# USB.net
KiCad netlist of a schematic drawn in Altium Designer
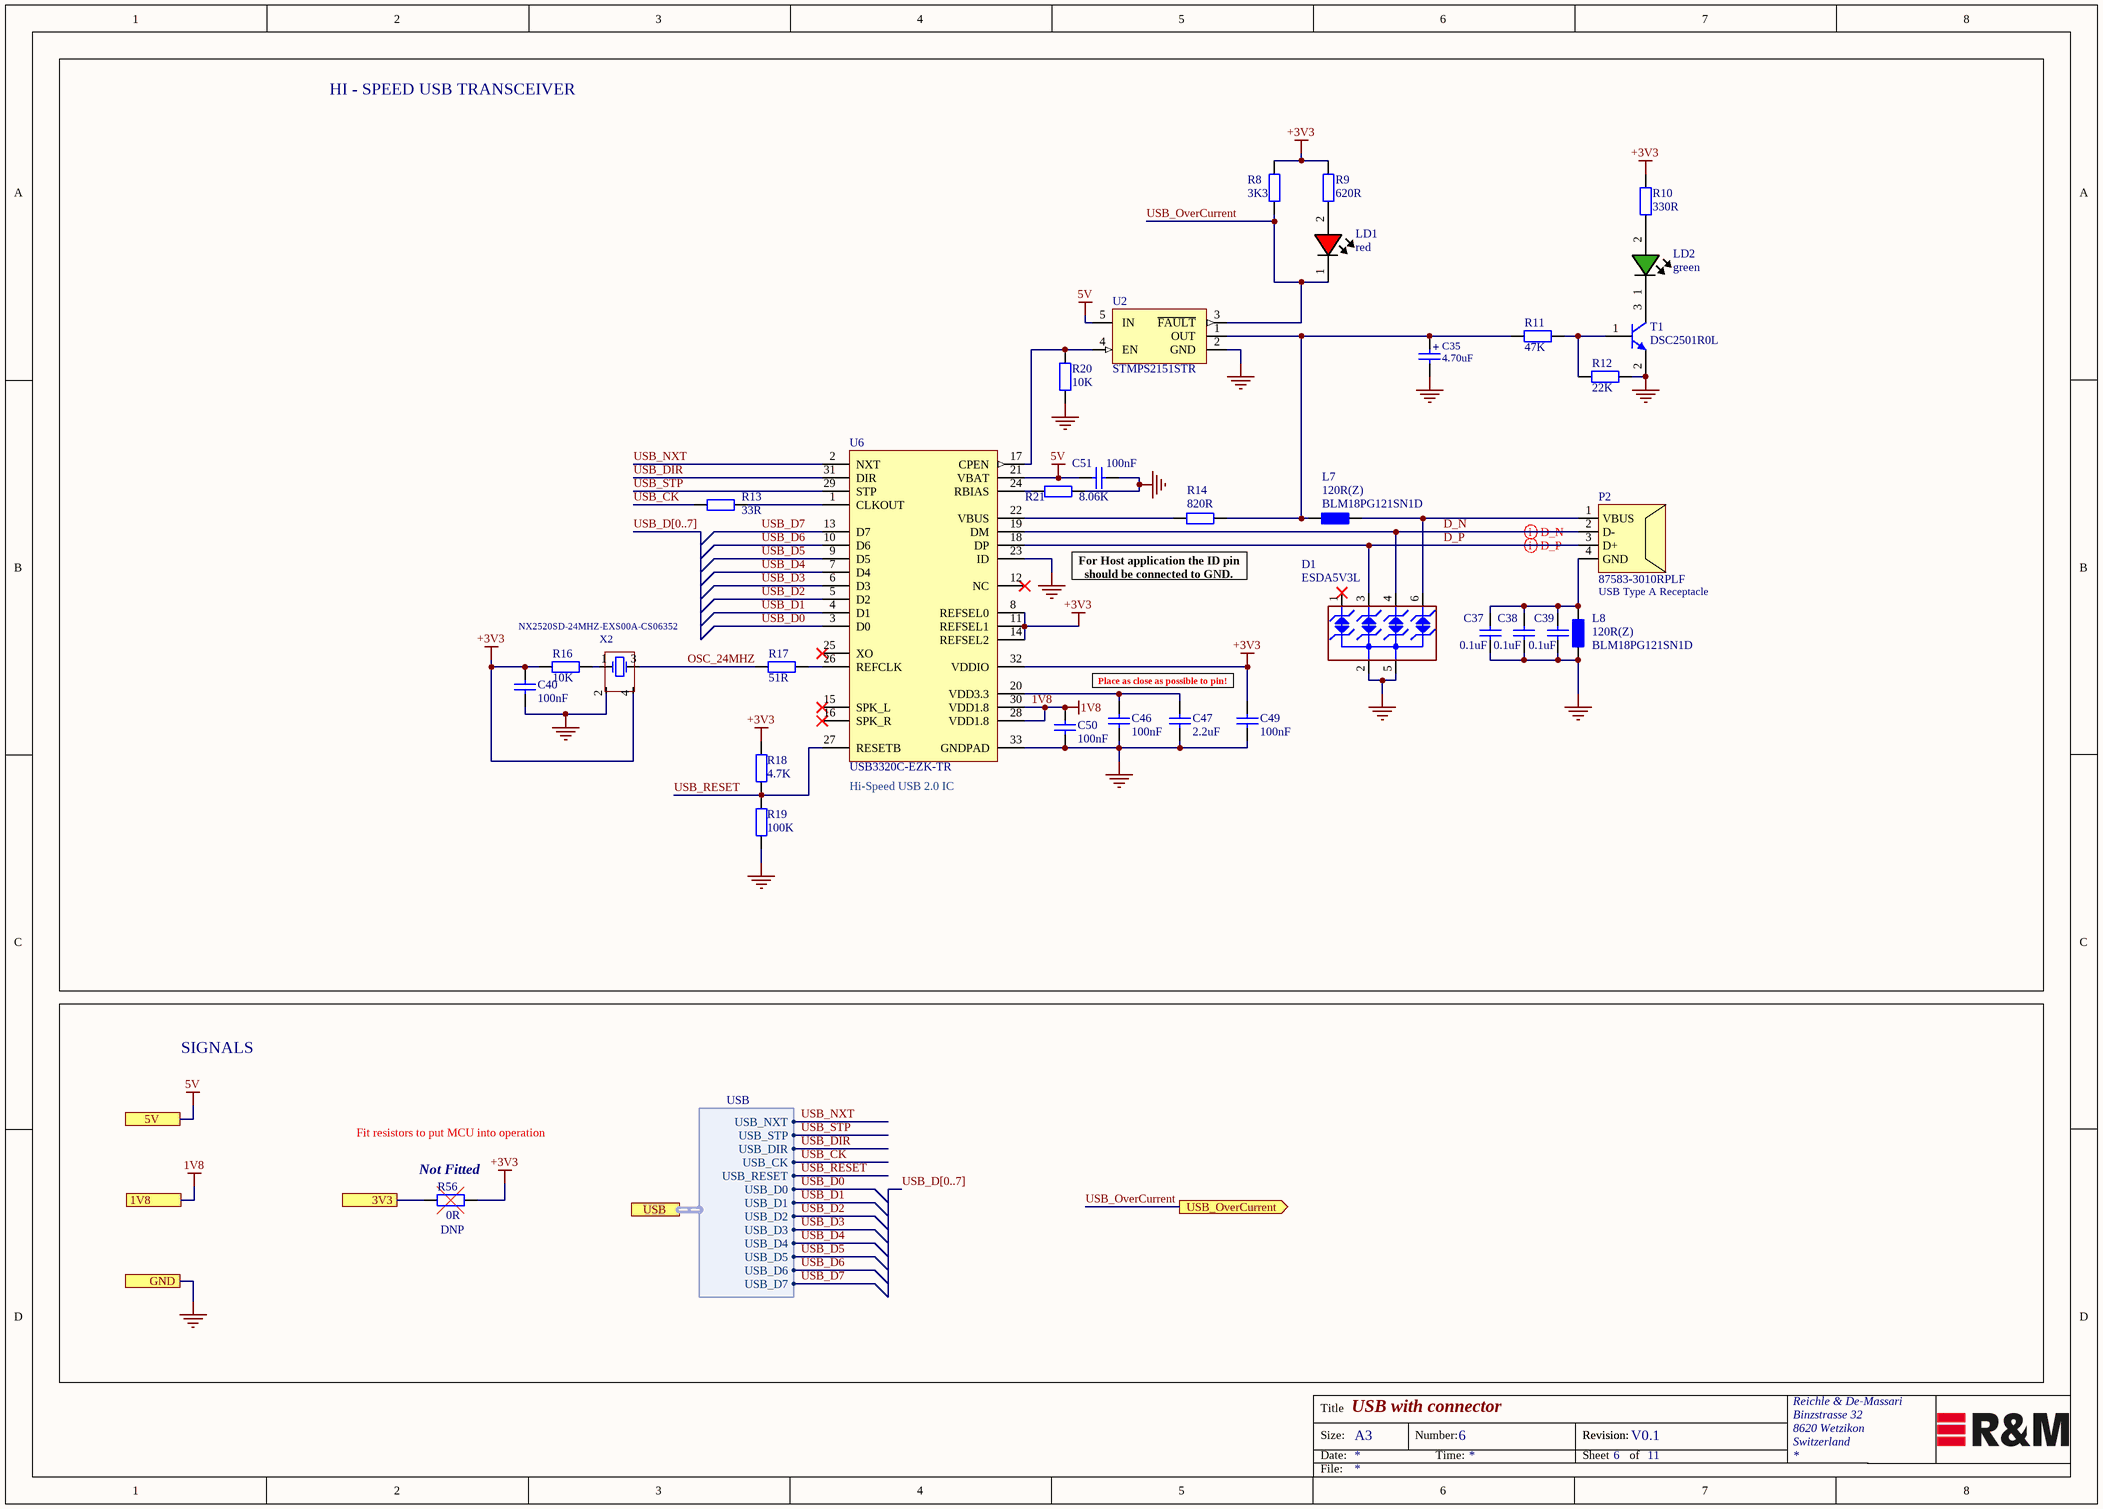
[diagram p0: USB.SchDoc]

(export (version "E")
  (design (tool "Eeschema 10.0.6"))
  (components
    (comp (ref "C35")
      (value "4.70uF")
      (footprint "CAPC1608X90")
      (description "4.7µF Molded Tantalum Capacitors 6.3V 0603 (1608 Metric) 7.5Ohm")
      (fields (field (name "MANUFACTURER") "AVX Corporation") (field (name "VOLTAGE") "6.3V"))
      (libsource (lib "RDM_ALT_SCH") (part "Cap_4.7uF_0603_6V3_Tantal"))
    )
    (comp (ref "C37")
      (value "0.1uF")
      (footprint "Ceramic Capacitor 0402 EIA")
      (description "0.1µF ±20% 16V Ceramic Capacitor X7R 0402 (1005 Metric)")
      (fields (field (name "TOLERANCE") "20%") (field (name "VOLTAGE") "16VDC"))
      (libsource (lib "RDM_ALT_SCH") (part "Cap_0.1uF_0402_16V"))
    )
    (comp (ref "C38")
      (value "0.1uF")
      (footprint "Ceramic Capacitor 0402 EIA")
      (description "0.1µF ±20% 16V Ceramic Capacitor X7R 0402 (1005 Metric)")
      (fields (field (name "TOLERANCE") "20%") (field (name "VOLTAGE") "16VDC"))
      (libsource (lib "RDM_ALT_SCH") (part "Cap_0.1uF_0402_16V"))
    )
    (comp (ref "C39")
      (value "0.1uF")
      (footprint "Ceramic Capacitor 0402 EIA")
      (description "0.1µF ±20% 16V Ceramic Capacitor X7R 0402 (1005 Metric)")
      (fields (field (name "TOLERANCE") "20%") (field (name "VOLTAGE") "16VDC"))
      (libsource (lib "RDM_ALT_SCH") (part "Cap_0.1uF_0402_16V"))
    )
    (comp (ref "C40")
      (value "100nF")
      (footprint "Ceramic Capacitor 0402 EIA")
      (description "0,1µF ±10% 10V Keramikkondensatoren X7R 0402 (1005 metrisch)")
      (fields (field (name "MANUFACTURER") "Samsung"))
      (libsource (lib "RDM_ALT_SCH") (part "Cap_100nF_0402_10V"))
    )
    (comp (ref "C46")
      (value "100nF")
      (footprint "Ceramic Capacitor 0402 EIA")
      (description "0,1µF ±10% 10V Keramikkondensatoren X7R 0402 (1005 metrisch)")
      (fields (field (name "MANUFACTURER") "Samsung"))
      (libsource (lib "RDM_ALT_SCH") (part "Cap_100nF_0402_10V"))
    )
    (comp (ref "C47")
      (value "2.2uF")
      (footprint "Ceramic Capacitor 0402 EIA")
      (description "Multilayer Ceramic Capacitors MLCC - SMD/SMT 0402 2.2uF 6.3volts *Derate Voltage/Temp")
      (fields (field (name "TOLERANCE") "±20%") (field (name "VOLTAGE") "6.3VDC"))
      (libsource (lib "RDM_ALT_SCH") (part "Cap_2.2uF_0402_6.3V"))
    )
    (comp (ref "C49")
      (value "100nF")
      (footprint "Ceramic Capacitor 0402 EIA")
      (description "0,1µF ±10% 10V Keramikkondensatoren X7R 0402 (1005 metrisch)")
      (fields (field (name "MANUFACTURER") "Samsung"))
      (libsource (lib "RDM_ALT_SCH") (part "Cap_100nF_0402_10V"))
    )
    (comp (ref "C50")
      (value "100nF")
      (footprint "Ceramic Capacitor 0402 EIA")
      (description "0,1µF ±10% 10V Keramikkondensatoren X7R 0402 (1005 metrisch)")
      (fields (field (name "MANUFACTURER") "Samsung"))
      (libsource (lib "RDM_ALT_SCH") (part "Cap_100nF_0402_10V"))
    )
    (comp (ref "C51")
      (value "100nF")
      (footprint "Ceramic Capacitor 0402 EIA")
      (description "0,1µF ±10% 10V Keramikkondensatoren X7R 0402 (1005 metrisch)")
      (fields (field (name "MANUFACTURER") "Samsung"))
      (libsource (lib "RDM_ALT_SCH") (part "Cap_100nF_0402_10V"))
    )
    (comp (ref "D1")
      (value "ESDA5V3L")
      (footprint "SOT23-6L")
      (description "Clamp Ipp Tvs Diode Surface Mount SOT-23-6 SMD, used e.g in ESD protection for USB")
      (fields (field (name "MANUFACTURER") "STMicroelectronics") (field (name "VOLTAGE") "6.1V"))
      (libsource (lib "RDM_ALT_SCH") (part "ESDA6V1BC6"))
    )
    (comp (ref "L7")
      (value "120R(Z)")
      (footprint "Inductor 0603 EIA")
      (description "120 Ohms @ 100MHz 1 Power Line Ferrite Bead 0603 (1608 Metric) 2A 50mOhm")
      (fields
        (field (name "MANUFACTURER") "Murata Electronics")
        (field (name "MANUFACTURER PARTNR") "BLM18PG121SN1D")
      )
      (libsource (lib "RDM_ALT_SCH") (part "Ferrit_Bead_0603_BLM18PG121SN1D"))
    )
    (comp (ref "L8")
      (value "120R(Z)")
      (footprint "Inductor 0603 EIA")
      (description "120 Ohms @ 100MHz 1 Power Line Ferrite Bead 0603 (1608 Metric) 2A 50mOhm")
      (fields
        (field (name "MANUFACTURER") "Murata Electronics")
        (field (name "MANUFACTURER PARTNR") "BLM18PG121SN1D")
      )
      (libsource (lib "") (part "Ferrit_Bead_0603_BLM18PG121SN1D_1"))
    )
    (comp (ref "LD1")
      (value "red")
      (footprint "LED_APHHS1005CGCK")
      (description "Red 630nm LED Indication - Discrete 1.95V 0402 (1005 Metric)")
      (fields (field (name "MANUFACTURER") "Kingbright") (field (name "VOLTAGE") "1.95V (forward)"))
      (libsource (lib "RDM_ALT_SCH") (part "LED_RED_0402"))
    )
    (comp (ref "LD2")
      (value "green")
      (footprint "LED_APHHS1005CGCK")
      (description "Green 570nm LED Indication - Discrete 2.1V 0402 (1005 Metric)")
      (fields (field (name "MANUFACTURER") "Kingbright") (field (name "VOLTAGE") "2.1V (forward)"))
      (libsource (lib "RDM_ALT_SCH") (part "LED_GREEN_0402"))
    )
    (comp (ref "P2")
      (value "87583-3010RPLF")
      (footprint "CONN_RCPT_USB_TYPE_A")
      (description "USB - A USB 2.0 Receptacle Connector 4 Position Surface Mount, Right Angle")
      (fields (field (name "MANUFACTURER") "Amphenol ICC"))
      (libsource (lib "RDM_ALT_SCH") (part "CONN_USB_TYPE_A_1"))
    )
    (comp (ref "R8")
      (value "3K3")
      (footprint "Resistor 0402 EIA")
      (description "3.3 kOhms ±0.1% 0.063W, 1/16W Chip Resistor 0402 (1005 Metric) Automotive AEC-Q200 Thin Film")
      (fields
        (field (name "MANUFACTURER") "Panasonic Electronic Components")
        (field (name "POWER") "0.063W, 1/16W")
      )
      (libsource (lib "RDM_ALT_SCH") (part "Res_3K3_0402"))
    )
    (comp (ref "R9")
      (value "620R")
      (footprint "Resistor 0402 EIA")
      (description "620Ohm, SMD 0402,  1/16W  0.5%")
      (fields (field (name "MANUFACTURER") "Susumu") (field (name "POWER") "62.5mW"))
      (libsource (lib "RDM_ALT_SCH") (part "Res_620R_0402"))
    )
    (comp (ref "R10")
      (value "330R")
      (footprint "Resistor 0402 EIA")
      (description "330 Ohms ±0.1% 0.063W, 1/16W Chip Resistor 0402 (1005 Metric) Automotive AEC-Q200 Thin Film")
      (fields
        (field (name "MANUFACTURER") "Panasonic Electronic Components")
        (field (name "POWER") "0.063W, 1/16W")
      )
      (libsource (lib "RDM_ALT_SCH") (part "Res_330R_0402"))
    )
    (comp (ref "R11")
      (value "47K")
      (footprint "Resistor 0402 EIA")
      (fields
        (field (name "TOLERANCE") "5%")
        (field (name "POWER") "62.5mW")
        (field (name "MANUFACTURER") "TE Connectivity")
      )
      (libsource (lib "RDM_ALT_SCH") (part "Res_47K_0402"))
    )
    (comp (ref "R12")
      (value "22K")
      (footprint "Resistor 0402 EIA")
      (description "22 kOhms ±5%  0402 (1005 metrisch) Thick Film")
      (fields (field (name "TOLERANCE") "5%") (field (name "POWER") "0.063W, 1/16W"))
      (libsource (lib "RDM_ALT_SCH") (part "Res_22K_0402"))
    )
    (comp (ref "R13")
      (value "33R")
      (footprint "Resistor 0402 EIA")
      (description "33 Ohms ±0.1% 0.063W, 1/16W Chip Resistor 0402 (1005 Metric) Thin Film")
      (fields (field (name "MANUFACTURER") "TE Connectivity") (field (name "POWER") "0.063W, 1/16W"))
      (libsource (lib "RDM_ALT_SCH") (part "Res_33R_0402"))
    )
    (comp (ref "R14")
      (value "820R")
      (footprint "Resistor 0402 EIA")
      (description "820 Ohms ±1% 0.1W, 1/10W 0402 Thick Film")
      (fields (field (name "TOLERANCE") "1%") (field (name "POWER") "0.1W, 1/10W"))
      (libsource (lib "RDM_ALT_SCH") (part "Res_820R_0402"))
    )
    (comp (ref "R16")
      (value "10K")
      (footprint "Resistor 0402 EIA")
      (description "SMD 10K ohm 1% 50V General Purpose")
      (fields (field (name "TOLERANCE") "1%") (field (name "POWER") "63mW"))
      (libsource (lib "") (part "Res_10K_0402_1"))
    )
    (comp (ref "R17")
      (value "51R")
      (footprint "Resistor 0402 EIA")
      (description "51 Ohms ±5% 0.063W, 1/16W Chip Resistor 0402 (1005 Metric) , Thick Film")
      (fields (field (name "TOLERANCE") "5%") (field (name "POWER") "62.5mW"))
      (libsource (lib "RDM_ALT_SCH") (part "Res_51R_0402"))
    )
    (comp (ref "R18")
      (value "4.7K")
      (footprint "Resistor 0402 EIA")
      (description "4.7 kOhms ±5% 0.063W, 1/16W Chip Resistor 0402 (1005 Metric) Moisture Resistant Thick Film")
      (fields (field (name "TOLERANCE") "±5%") (field (name "POWER") "0.063W, 1/16W"))
      (libsource (lib "RDM_ALT_SCH") (part "Res_4K7_0402"))
    )
    (comp (ref "R19")
      (value "100K")
      (footprint "Resistor 0402 EIA")
      (description "100 kOhms ±0,1% 0,063W, 1/16W Chip-Widerstand 0402 (1005 metrisch) Dünnschicht")
      (fields (field (name "TOLERANCE") "±0.1%") (field (name "POWER") "0,063W, 1/16W"))
      (libsource (lib "RDM_ALT_SCH") (part "Res_100K_0402"))
    )
    (comp (ref "R20")
      (value "10K")
      (footprint "Resistor 0402 EIA")
      (description "SMD 10K ohm 1% 50V General Purpose")
      (fields (field (name "TOLERANCE") "1%") (field (name "POWER") "63mW"))
      (libsource (lib "RDM_ALT_SCH") (part "Res_10K_0402"))
    )
    (comp (ref "R21")
      (value "8.06K")
      (footprint "Resistor 0402 EIA")
      (description "8.06 kOhms ±1% 0.063W, 1/16W Chip Resistor 0402 (1005 Metric) Moisture Resistant Thick Film")
      (fields (field (name "TOLERANCE") "±1%") (field (name "POWER") "0.063W, 1/16W"))
      (libsource (lib "RDM_ALT_SCH") (part "Res_8K06_0402"))
    )
    (comp (ref "R56")
      (value "DNP")
      (footprint "Resistor 0805 EIA")
      (description "Resistor: do not populate")
      (fields (field (name "MANUFACTURER") "do not populate"))
      (libsource (lib "RDM_ALT_SCH") (part "Res_DNP_0805"))
    )
    (comp (ref "T1")
      (value "DSC2501R0L")
      (footprint "SOT-23/TO-236AA")
      (description "Bipolar (BJT) Transistor NPN 20V 500mA 150MHz 200mW Surface Mount Mini3-G3-B-B")
      (fields (field (name "MANUFACTURER") "Panasonic Electronic Components") (field (name "VOLTAGE") "20V"))
      (libsource (lib "RDM_ALT_SCH") (part "BJT_NPN_20V"))
    )
    (comp (ref "U2")
      (value "STMPS2151STR")
      (footprint "SOT23-5L")
      (description "Power Switch/Driver 1:1 N-Kanal 500mA SOT-23-5,  STMicroelectronics")
      (fields (field (name "MANUFACTURER") "STMicroelectronics") (field (name "VOLTAGE") "2,7V ~ 5,5V"))
      (libsource (lib "RDM_ALT_SCH") (part "STMPS2151STR"))
    )
    (comp (ref "U6")
      (value "USB3320C-EZK-TR")
      (footprint "QFN32_0R5_5X5")
      (description "USB3320C,  Hi-Speed USB Host, Device or OTG PHY with ULPI Low Pin Interface,  32-QFN (5x5)")
      (fields (field (name "MANUFACTURER") "Microchip") (field (name "VOLTAGE") "1.8V ~ 3.3V"))
      (libsource (lib "RDM_ALT_SCH") (part "USB3320C-EZK"))
    )
    (comp (ref "X2")
      (value "NX2520SD-24MHZ-EXS00A-CS06352")
      (footprint "NX2520SD-24MHZ-EX")
      (description "24MHz ±15ppm Crystal 12pF 50 Ohms 4-SMD, No Lead")
      (fields (field (name "MANUFACTURER") "NDK America, Inc."))
      (libsource (lib "RDM_ALT_SCH") (part "CRYSTAL_4Pad_NX2520SD-24MHZ"))
    )
  )
  (nets
    (net (code "2") (name "+3V3") (class "Default")
      (node (ref "C40") (pin "2") (pinfunction "2_2") (pintype "passive"))
      (node (ref "C49") (pin "2") (pinfunction "2_2") (pintype "passive"))
      (node (ref "R10") (pin "1") (pinfunction "1_1") (pintype "passive"))
      (node (ref "R16") (pin "1") (pinfunction "1_1") (pintype "passive"))
      (node (ref "R18") (pin "1") (pinfunction "1_1") (pintype "passive"))
      (node (ref "R56") (pin "2") (pinfunction "2_2") (pintype "passive"))
      (node (ref "R8") (pin "2") (pinfunction "2_2") (pintype "passive"))
      (node (ref "R9") (pin "1") (pinfunction "1_1") (pintype "passive"))
      (node (ref "U6") (pin "11") (pinfunction "REFSEL1_11") (pintype "passive"))
      (node (ref "U6") (pin "14") (pinfunction "REFSEL2_14") (pintype "passive"))
      (node (ref "U6") (pin "32") (pinfunction "VDDIO_32") (pintype "passive"))
      (node (ref "U6") (pin "8") (pinfunction "REFSEL0_8") (pintype "passive"))
      (node (ref "X2") (pin "4") (pinfunction "OSC3_4") (pintype "passive"))
    )
    (net (code "3") (name "/3V3") (class "Default")
      (node (ref "R56") (pin "1") (pinfunction "1_1") (pintype "passive"))
    )
    (net (code "4") (name "/D_N") (class "Default")
      (node (ref "D1") (pin "4") (pinfunction "IO3_4") (pintype "passive"))
      (node (ref "P2") (pin "2") (pinfunction "D-_2") (pintype "passive"))
      (node (ref "U6") (pin "19") (pinfunction "DM_19") (pintype "passive"))
    )
    (net (code "5") (name "/D_P") (class "Default")
      (node (ref "D1") (pin "3") (pinfunction "GND_3") (pintype "passive"))
      (node (ref "P2") (pin "3") (pinfunction "D+_3") (pintype "passive"))
      (node (ref "U6") (pin "18") (pinfunction "DP_18") (pintype "passive"))
    )
    (net (code "6") (name "/OSC_24MHZ") (class "Default")
      (node (ref "R17") (pin "1") (pinfunction "1_1") (pintype "passive"))
      (node (ref "X2") (pin "3") (pinfunction "OSC2_3") (pintype "passive"))
    )
    (net (code "7") (name "/USB_CK") (class "Default")
      (node (ref "R13") (pin "1") (pinfunction "1_1") (pintype "passive"))
    )
    (net (code "8") (name "/USB_D0") (class "Default")
      (node (ref "U6") (pin "3") (pinfunction "D0_3") (pintype "passive"))
    )
    (net (code "9") (name "/USB_D1") (class "Default")
      (node (ref "U6") (pin "4") (pinfunction "D1_4") (pintype "passive"))
    )
    (net (code "10") (name "/USB_D2") (class "Default")
      (node (ref "U6") (pin "5") (pinfunction "D2_5") (pintype "passive"))
    )
    (net (code "11") (name "/USB_D3") (class "Default")
      (node (ref "U6") (pin "6") (pinfunction "D3_6") (pintype "passive"))
    )
    (net (code "12") (name "/USB_D4") (class "Default")
      (node (ref "U6") (pin "7") (pinfunction "D4_7") (pintype "passive"))
    )
    (net (code "13") (name "/USB_D5") (class "Default")
      (node (ref "U6") (pin "9") (pinfunction "D5_9") (pintype "passive"))
    )
    (net (code "14") (name "/USB_D6") (class "Default")
      (node (ref "U6") (pin "10") (pinfunction "D6_10") (pintype "passive"))
    )
    (net (code "15") (name "/USB_D7") (class "Default")
      (node (ref "U6") (pin "13") (pinfunction "D7_13") (pintype "passive"))
    )
    (net (code "16") (name "/USB_DIR") (class "Default")
      (node (ref "U6") (pin "31") (pinfunction "DIR_31") (pintype "passive"))
    )
    (net (code "18") (name "/USB_NXT") (class "Default")
      (node (ref "U6") (pin "2") (pinfunction "NXT_2") (pintype "passive"))
    )
    (net (code "19") (name "/USB_OverCurrent") (class "Default")
      (node (ref "LD1") (pin "1") (pinfunction "1_1") (pintype "passive"))
      (node (ref "R8") (pin "1") (pinfunction "1_1") (pintype "passive"))
      (node (ref "U2") (pin "3") (pinfunction "~{FAULT}_3") (pintype "output"))
    )
    (net (code "20") (name "/USB_RESET") (class "Default")
      (node (ref "R18") (pin "2") (pinfunction "2_2") (pintype "passive"))
      (node (ref "R19") (pin "1") (pinfunction "1_1") (pintype "passive"))
      (node (ref "U6") (pin "27") (pinfunction "RESETB_27") (pintype "passive"))
    )
    (net (code "21") (name "/USB_STP") (class "Default")
      (node (ref "U6") (pin "29") (pinfunction "STP_29") (pintype "passive"))
    )
    (net (code "23") (name "1V8") (class "Default")
      (node (ref "C50") (pin "2") (pinfunction "2_2") (pintype "passive"))
      (node (ref "U6") (pin "28") (pinfunction "VDD1.8_28") (pintype "passive"))
      (node (ref "U6") (pin "30") (pinfunction "VDD1.8_30") (pintype "passive"))
    )
    (net (code "24") (name "5V") (class "Default")
      (node (ref "C51") (pin "2") (pinfunction "2_2") (pintype "passive"))
      (node (ref "U2") (pin "5") (pinfunction "IN_5") (pintype "passive"))
      (node (ref "U6") (pin "21") (pinfunction "VBAT_21") (pintype "passive"))
    )
    (net (code "25") (name "GND") (class "Default")
      (node (ref "C35") (pin "2") (pinfunction "Neg_2") (pintype "passive"))
      (node (ref "C37") (pin "1") (pinfunction "1_1") (pintype "passive"))
      (node (ref "C38") (pin "1") (pinfunction "1_1") (pintype "passive"))
      (node (ref "C39") (pin "1") (pinfunction "1_1") (pintype "passive"))
      (node (ref "C40") (pin "1") (pinfunction "1_1") (pintype "passive"))
      (node (ref "C46") (pin "1") (pinfunction "1_1") (pintype "passive"))
      (node (ref "C47") (pin "1") (pinfunction "1_1") (pintype "passive"))
      (node (ref "C49") (pin "1") (pinfunction "1_1") (pintype "passive"))
      (node (ref "C50") (pin "1") (pinfunction "1_1") (pintype "passive"))
      (node (ref "C51") (pin "1") (pinfunction "1_1") (pintype "passive"))
      (node (ref "D1") (pin "2") (pinfunction "IO2_2") (pintype "passive"))
      (node (ref "D1") (pin "5") (pinfunction "IO4_5") (pintype "passive"))
      (node (ref "L8") (pin "1") (pinfunction "1_1") (pintype "passive"))
      (node (ref "R12") (pin "2") (pinfunction "2_2") (pintype "passive"))
      (node (ref "R19") (pin "2") (pinfunction "2_2") (pintype "passive"))
      (node (ref "R20") (pin "2") (pinfunction "2_2") (pintype "passive"))
      (node (ref "R21") (pin "2") (pinfunction "2_2") (pintype "passive"))
      (node (ref "T1") (pin "2") (pinfunction "E_2") (pintype "passive"))
      (node (ref "U2") (pin "2") (pinfunction "GND_2") (pintype "passive"))
      (node (ref "U6") (pin "23") (pinfunction "ID_23") (pintype "passive"))
      (node (ref "U6") (pin "33") (pinfunction "GNDPAD_33") (pintype "passive"))
      (node (ref "X2") (pin "2") (pinfunction "OSC2_2") (pintype "passive"))
    )
    (net (code "26") (name "Net-(C35-Pos)") (class "Default")
      (node (ref "C35") (pin "1") (pinfunction "Pos_1") (pintype "passive"))
      (node (ref "L7") (pin "1") (pinfunction "1_1") (pintype "passive"))
      (node (ref "R11") (pin "1") (pinfunction "1_1") (pintype "passive"))
      (node (ref "R14") (pin "2") (pinfunction "2_2") (pintype "passive"))
      (node (ref "U2") (pin "1") (pinfunction "OUT_1") (pintype "passive"))
    )
    (net (code "27") (name "Net-(D1-NC)") (class "Default")
      (node (ref "D1") (pin "6") (pinfunction "NC_6") (pintype "passive"))
      (node (ref "L7") (pin "2") (pinfunction "2_2") (pintype "passive"))
      (node (ref "P2") (pin "1") (pinfunction "VBUS_1") (pintype "passive"))
    )
    (net (code "28") (name "Net-(LD2-Pad2)") (class "Default")
      (node (ref "LD2") (pin "2") (pinfunction "2_2") (pintype "passive"))
      (node (ref "R10") (pin "2") (pinfunction "2_2") (pintype "passive"))
    )
    (net (code "29") (name "Net-(P2-GND)") (class "Default")
      (node (ref "C37") (pin "2") (pinfunction "2_2") (pintype "passive"))
      (node (ref "C38") (pin "2") (pinfunction "2_2") (pintype "passive"))
      (node (ref "C39") (pin "2") (pinfunction "2_2") (pintype "passive"))
      (node (ref "L8") (pin "2") (pinfunction "2_2") (pintype "passive"))
      (node (ref "P2") (pin "4") (pinfunction "GND_4") (pintype "passive"))
    )
    (net (code "30") (name "Net-(T1-B)") (class "Default")
      (node (ref "R11") (pin "2") (pinfunction "2_2") (pintype "passive"))
      (node (ref "R12") (pin "1") (pinfunction "1_1") (pintype "passive"))
      (node (ref "T1") (pin "1") (pinfunction "B_1") (pintype "passive"))
    )
    (net (code "31") (name "Net-(U2-EN)") (class "Default")
      (node (ref "R20") (pin "1") (pinfunction "1_1") (pintype "passive"))
      (node (ref "U2") (pin "4") (pinfunction "EN_4") (pintype "input"))
      (node (ref "U6") (pin "17") (pinfunction "CPEN_17") (pintype "output"))
    )
    (net (code "32") (name "Net-(U6-CLKOUT)") (class "Default")
      (node (ref "R13") (pin "2") (pinfunction "2_2") (pintype "passive"))
      (node (ref "U6") (pin "1") (pinfunction "CLKOUT_1") (pintype "passive"))
    )
    (net (code "33") (name "Net-(U6-RBIAS)") (class "Default")
      (node (ref "R21") (pin "1") (pinfunction "1_1") (pintype "passive"))
      (node (ref "U6") (pin "24") (pinfunction "RBIAS_24") (pintype "passive"))
    )
    (net (code "34") (name "Net-(U6-REFCLK)") (class "Default")
      (node (ref "R17") (pin "2") (pinfunction "2_2") (pintype "passive"))
      (node (ref "U6") (pin "26") (pinfunction "REFCLK_26") (pintype "passive"))
    )
    (net (code "35") (name "Net-(U6-VBUS)") (class "Default")
      (node (ref "R14") (pin "1") (pinfunction "1_1") (pintype "passive"))
      (node (ref "U6") (pin "22") (pinfunction "VBUS_22") (pintype "passive"))
    )
    (net (code "36") (name "Net-(U6-VDD3.3)") (class "Default")
      (node (ref "C46") (pin "2") (pinfunction "2_2") (pintype "passive"))
      (node (ref "C47") (pin "2") (pinfunction "2_2") (pintype "passive"))
      (node (ref "U6") (pin "20") (pinfunction "VDD3.3_20") (pintype "passive"))
    )
    (net (code "37") (name "Net-(X2-OSC1)") (class "Default")
      (node (ref "R16") (pin "2") (pinfunction "2_2") (pintype "passive"))
      (node (ref "X2") (pin "1") (pinfunction "OSC1_1") (pintype "passive"))
    )
    (net (code "38") (name "unconnected-(D1-IO1-Pad1)") (class "Default")
      (node (ref "D1") (pin "1") (pinfunction "IO1_1") (pintype "passive+no_connect"))
    )
    (net (code "39") (name "unconnected-(LD1-Pad2)") (class "Default")
      (node (ref "LD1") (pin "2") (pinfunction "2_2") (pintype "passive"))
    )
    (net (code "40") (name "unconnected-(LD2-Pad1)") (class "Default")
      (node (ref "LD2") (pin "1") (pinfunction "1_1") (pintype "passive"))
    )
    (net (code "41") (name "unconnected-(R9-Pad2)") (class "Default")
      (node (ref "R9") (pin "2") (pinfunction "2_2") (pintype "passive"))
    )
    (net (code "42") (name "unconnected-(T1-C-Pad3)") (class "Default")
      (node (ref "T1") (pin "3") (pinfunction "C_3") (pintype "passive"))
    )
    (net (code "43") (name "unconnected-(U6-NC-Pad12)") (class "Default")
      (node (ref "U6") (pin "12") (pinfunction "NC_12") (pintype "passive+no_connect"))
    )
    (net (code "44") (name "unconnected-(U6-SPK_L-Pad15)") (class "Default")
      (node (ref "U6") (pin "15") (pinfunction "SPK_L_15") (pintype "passive+no_connect"))
    )
    (net (code "45") (name "unconnected-(U6-SPK_R-Pad16)") (class "Default")
      (node (ref "U6") (pin "16") (pinfunction "SPK_R_16") (pintype "passive+no_connect"))
    )
    (net (code "46") (name "unconnected-(U6-XO-Pad25)") (class "Default")
      (node (ref "U6") (pin "25") (pinfunction "XO_25") (pintype "passive+no_connect"))
    )
  )
)
